# riego.net
KiCad netlist of a schematic drawn in Altium Designer
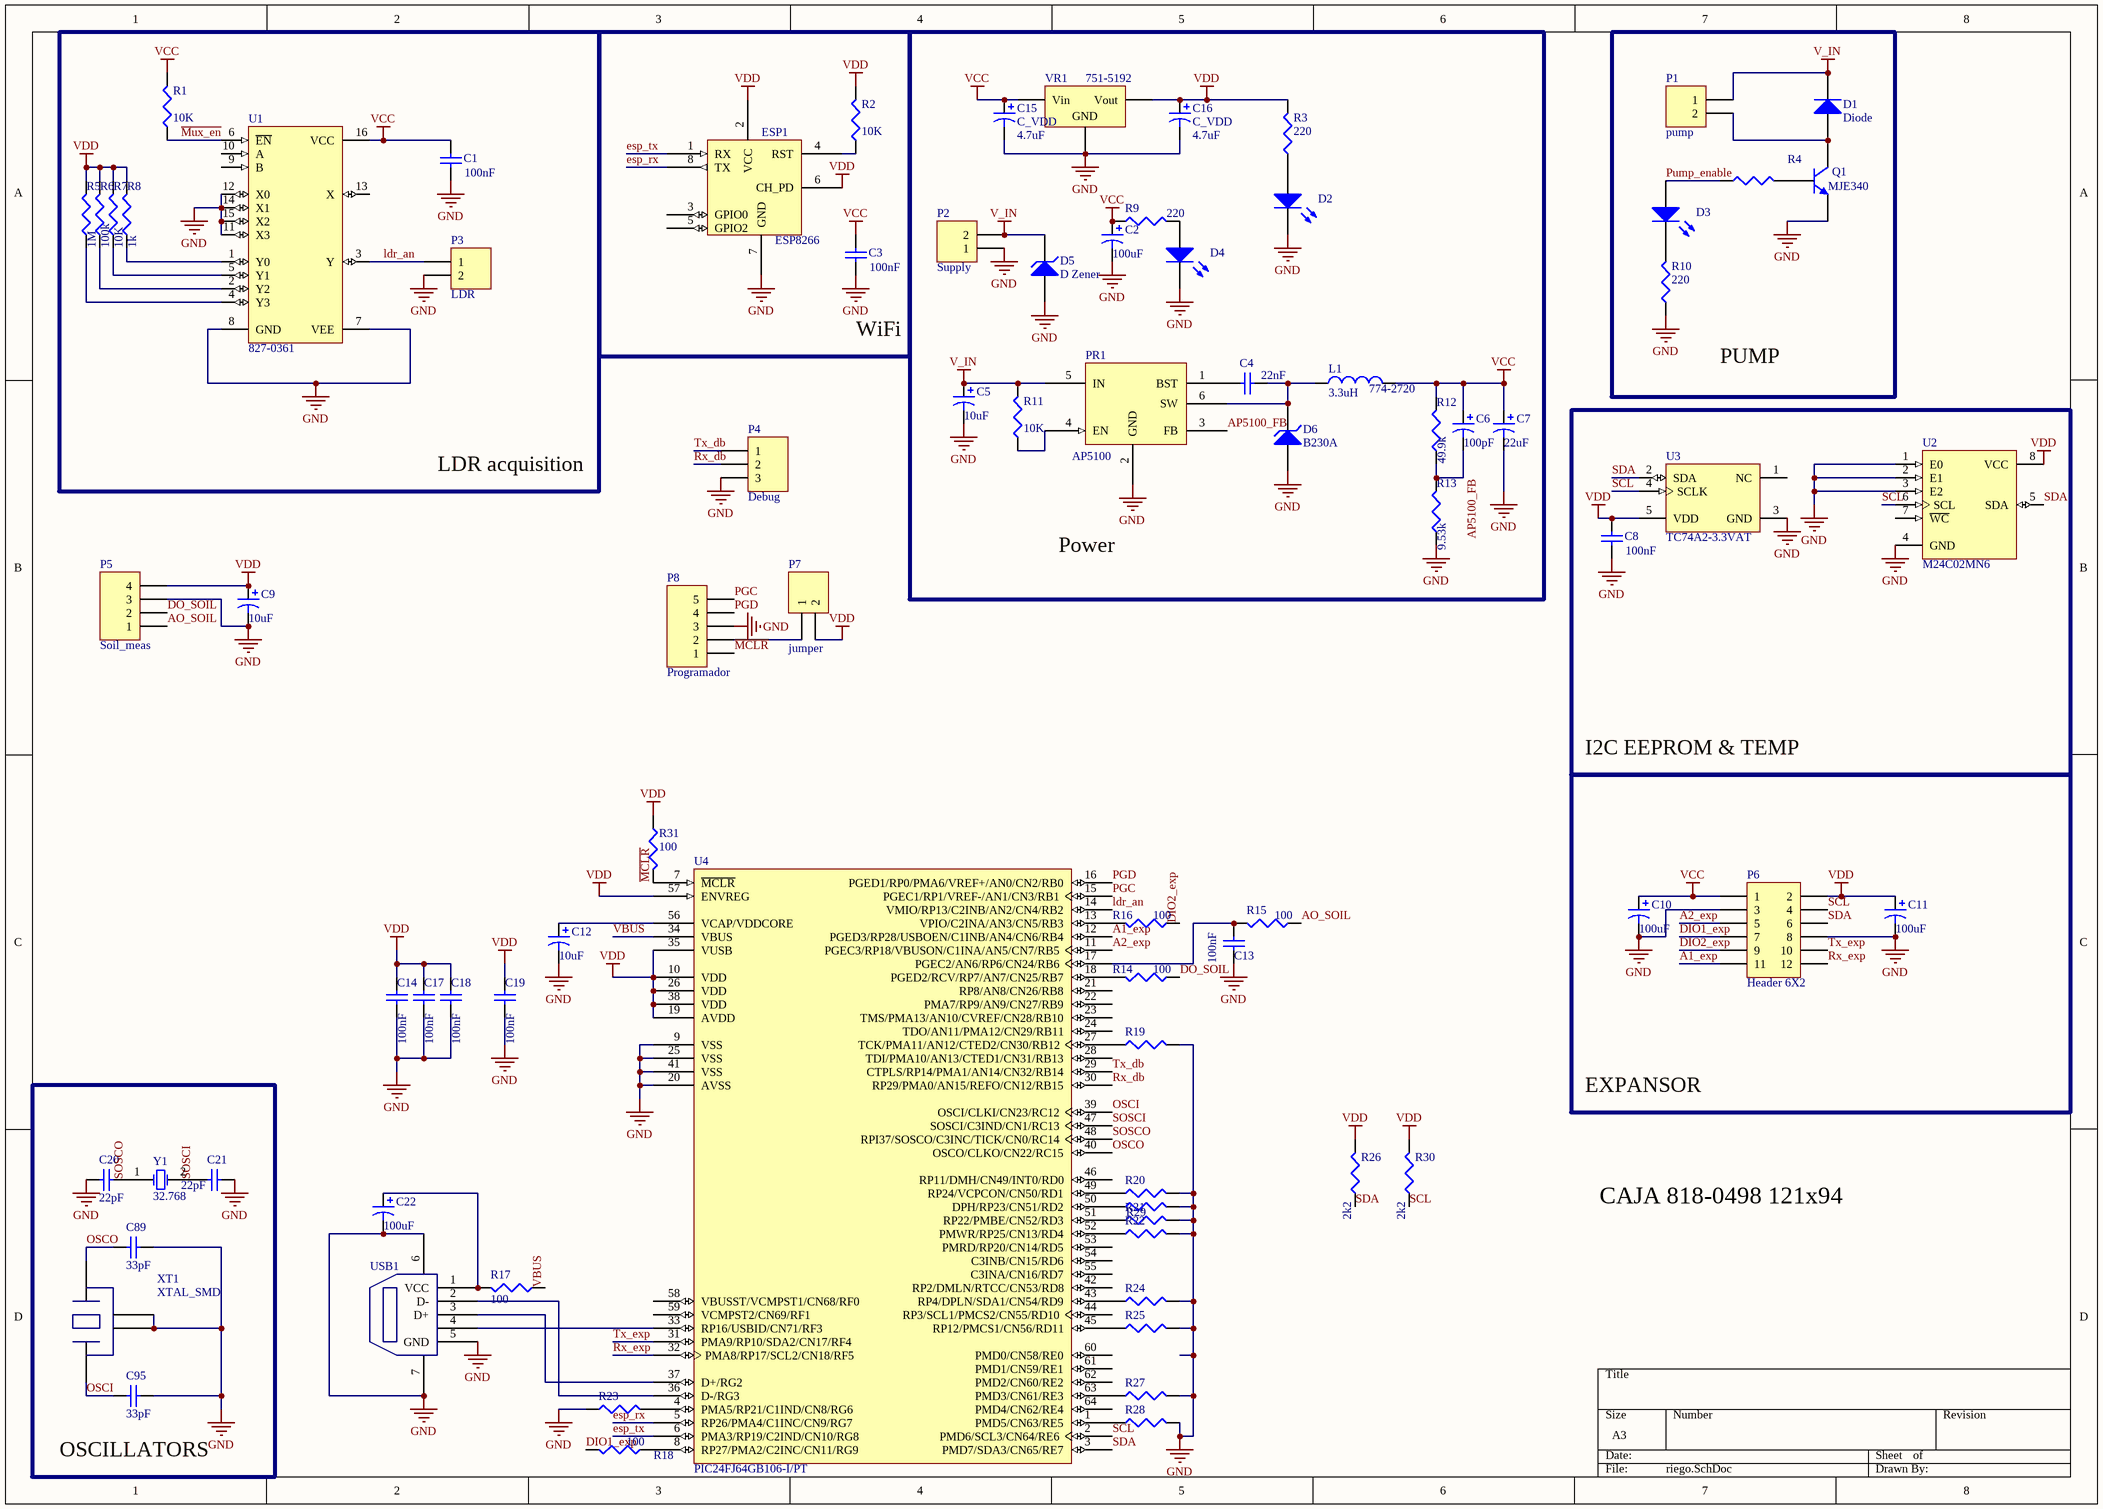
[diagram p0: riego.SchDoc]

(export (version "E")
  (design (tool "Eeschema 10.0.6"))
  (components
    (comp (ref "C1")
      (value "100nF")
      (footprint "CAPC1608L")
      (description "Capacitor (Semiconductor SIM Model)")
      (fields (field (name "Comment") "Cap Semi") (field (name "PUBLISHER") "Altium Limited"))
      (libsource (lib "Miscellaneous Devices") (part "Cap Semi"))
    )
    (comp (ref "C2")
      (value "100uF")
      (footprint "TC3528-1411")
      (description "Polarized Capacitor (Radial)")
      (fields (field (name "PUBLISHER") "Altium Limited"))
      (libsource (lib "Miscellaneous Devices") (part "Cap Pol1"))
    )
    (comp (ref "C3")
      (value "100nF")
      (footprint "CAPC1608L")
      (description "Capacitor (Semiconductor SIM Model)")
      (fields (field (name "Comment") "Cap Semi") (field (name "PUBLISHER") "Altium Limited"))
      (libsource (lib "Miscellaneous Devices") (part "Cap Semi"))
    )
    (comp (ref "C4")
      (value "22nF")
      (footprint "CAPC1608L")
      (description "Capacitor (Semiconductor SIM Model)")
      (fields (field (name "Comment") "Cap Semi") (field (name "PUBLISHER") "Altium Limited"))
      (libsource (lib "Miscellaneous Devices") (part "Cap Semi"))
    )
    (comp (ref "C5")
      (value "10uF")
      (footprint "TC3528-1411")
      (description "Polarized Capacitor (Radial)")
      (fields (field (name "PUBLISHER") "Altium Limited"))
      (libsource (lib "Miscellaneous Devices") (part "Cap Pol1"))
    )
    (comp (ref "C6")
      (value "100pF")
      (footprint "TC3528-1411")
      (description "Polarized Capacitor (Radial)")
      (fields (field (name "PUBLISHER") "Altium Limited"))
      (libsource (lib "Miscellaneous Devices") (part "Cap Pol1"))
    )
    (comp (ref "C7")
      (value "22uF")
      (footprint "TC3528-1411")
      (description "Polarized Capacitor (Radial)")
      (fields (field (name "PUBLISHER") "Altium Limited"))
      (libsource (lib "Miscellaneous Devices") (part "Cap Pol1"))
    )
    (comp (ref "C8")
      (value "100nF")
      (footprint "CAPC1608L")
      (description "Capacitor (Semiconductor SIM Model)")
      (fields (field (name "Comment") "Cap Semi") (field (name "PUBLISHER") "Altium Limited"))
      (libsource (lib "Miscellaneous Devices") (part "Cap Semi"))
    )
    (comp (ref "C9")
      (value "10uF")
      (footprint "TC3528-1411")
      (description "Polarized Capacitor (Radial)")
      (fields (field (name "PUBLISHER") "Altium Limited"))
      (libsource (lib "Miscellaneous Devices") (part "Cap Pol1"))
    )
    (comp (ref "C10")
      (value "100uF")
      (footprint "TC3528-1411")
      (description "Polarized Capacitor (Radial)")
      (fields (field (name "PUBLISHER") "Altium Limited"))
      (libsource (lib "Miscellaneous Devices") (part "Cap Pol1"))
    )
    (comp (ref "C11")
      (value "100uF")
      (footprint "TC3528-1411")
      (description "Polarized Capacitor (Radial)")
      (fields (field (name "PUBLISHER") "Altium Limited"))
      (libsource (lib "Miscellaneous Devices") (part "Cap Pol1"))
    )
    (comp (ref "C12")
      (value "10uF")
      (footprint "TC3528-1411")
      (description "Polarized Capacitor (Radial)")
      (fields (field (name "PUBLISHER") "Altium Limited"))
      (libsource (lib "Miscellaneous Devices") (part "Cap Pol1"))
    )
    (comp (ref "C13")
      (value "100nF")
      (footprint "CAPC1608L")
      (description "Capacitor (Semiconductor SIM Model)")
      (fields (field (name "Comment") "Cap Semi") (field (name "PUBLISHER") "Altium Limited"))
      (libsource (lib "Miscellaneous Devices") (part "Cap Semi"))
    )
    (comp (ref "C14")
      (value "100nF")
      (footprint "CAPC1608L")
      (description "Capacitor (Semiconductor SIM Model)")
      (fields (field (name "Comment") "Cap Semi") (field (name "PUBLISHER") "Altium Limited"))
      (libsource (lib "Miscellaneous Devices") (part "Cap Semi"))
    )
    (comp (ref "C15")
      (value "C_VDD")
      (footprint "CAPC1608N")
      (description "Polarized Capacitor (Radial)")
      (fields (field (name "ALTIUM_VALUE") "4.7uF") (field (name "PUBLISHER") "Altium Limited"))
      (libsource (lib "Miscellaneous Devices") (part "Cap Pol1"))
    )
    (comp (ref "C16")
      (value "C_VDD")
      (footprint "CAPC1608L")
      (description "Polarized Capacitor (Radial)")
      (fields (field (name "ALTIUM_VALUE") "4.7uF") (field (name "PUBLISHER") "Altium Limited"))
      (libsource (lib "Miscellaneous Devices") (part "Cap Pol1"))
    )
    (comp (ref "C17")
      (value "100nF")
      (footprint "CAPC1608L")
      (description "Capacitor (Semiconductor SIM Model)")
      (fields (field (name "Comment") "Cap Semi") (field (name "PUBLISHER") "Altium Limited"))
      (libsource (lib "Miscellaneous Devices") (part "Cap Semi"))
    )
    (comp (ref "C18")
      (value "100nF")
      (footprint "CAPC1608L")
      (description "Capacitor (Semiconductor SIM Model)")
      (fields (field (name "Comment") "Cap Semi") (field (name "PUBLISHER") "Altium Limited"))
      (libsource (lib "Miscellaneous Devices") (part "Cap Semi"))
    )
    (comp (ref "C19")
      (value "100nF")
      (footprint "CAPC1608L")
      (description "Capacitor (Semiconductor SIM Model)")
      (fields (field (name "Comment") "Cap Semi") (field (name "PUBLISHER") "Altium Limited"))
      (libsource (lib "Miscellaneous Devices") (part "Cap Semi"))
    )
    (comp (ref "C20")
      (value "22pF")
      (footprint "C1206")
      (description "Capacitor (Semiconductor SIM Model)")
      (fields (field (name "Comment") "Cap Semi") (field (name "PUBLISHER") "Altium Limited"))
      (libsource (lib "Miscellaneous Devices") (part "Cap Semi"))
    )
    (comp (ref "C21")
      (value "22pF")
      (footprint "C1206")
      (description "Capacitor (Semiconductor SIM Model)")
      (fields (field (name "Comment") "Cap Semi") (field (name "PUBLISHER") "Altium Limited"))
      (libsource (lib "Miscellaneous Devices") (part "Cap Semi"))
    )
    (comp (ref "C22")
      (value "100uF")
      (footprint "TC3528-1411")
      (description "Polarized Capacitor (Radial)")
      (fields (field (name "PUBLISHER") "Altium Limited"))
      (libsource (lib "Miscellaneous Devices") (part "Cap Pol1"))
    )
    (comp (ref "C89")
      (value "33pF")
      (footprint "C1206")
      (description "Capacitor (Semiconductor SIM Model)")
      (fields (field (name "Comment") "Cap Semi") (field (name "PUBLISHER") "Altium Limited"))
      (libsource (lib "Miscellaneous Devices") (part "Cap Semi"))
    )
    (comp (ref "C95")
      (value "33pF")
      (footprint "C1206")
      (description "Capacitor (Semiconductor SIM Model)")
      (fields (field (name "Comment") "Cap Semi") (field (name "PUBLISHER") "Altium Limited"))
      (libsource (lib "Miscellaneous Devices") (part "Cap Semi"))
    )
    (comp (ref "D1")
      (value "Diode")
      (footprint "CD4532-1812")
      (description "Default Diode")
      (fields (field (name "PUBLISHER") "Altium Limited"))
      (libsource (lib "Miscellaneous Devices") (part "Diode"))
    )
    (comp (ref "D2")
      (value "Ledred")
      (footprint "CD1608-0603")
      (description "Typical BLUE SiC LED")
      (fields (field (name "PUBLISHER") "Altium Limited"))
      (libsource (lib "Miscellaneous Devices") (part "LED3"))
    )
    (comp (ref "D3")
      (value "Ledred")
      (footprint "CD1608-0603")
      (description "Typical BLUE SiC LED")
      (fields (field (name "PUBLISHER") "Altium Limited"))
      (libsource (lib "Miscellaneous Devices") (part "LED3"))
    )
    (comp (ref "D4")
      (value "Ledgreen")
      (footprint "CD1608-0603")
      (description "Typical BLUE SiC LED")
      (fields (field (name "PUBLISHER") "Altium Limited"))
      (libsource (lib "Miscellaneous Devices") (part "LED3"))
    )
    (comp (ref "D5")
      (value "D Zener")
      (footprint "CD4532-1812")
      (description "Zener Diode")
      (fields (field (name "PUBLISHER") "Altium Limited"))
      (libsource (lib "Miscellaneous Devices") (part "D Zener"))
    )
    (comp (ref "D6")
      (value "B230A")
      (footprint "CD4532-1812")
      (description "Zener Diode")
      (fields (field (name "PUBLISHER") "Altium Limited"))
      (libsource (lib "Miscellaneous Devices") (part "D Zener"))
    )
    (comp (ref "ESP1") (value "ESP8266") (footprint "ESP8266") (libsource (lib "Mylib") (part "ESP8266")))
    (comp (ref "L1")
      (value "774-2720")
      (footprint "INDC5750N")
      (description "Inductor")
      (fields (field (name "ALTIUM_VALUE") "3.3uH") (field (name "PUBLISHER") "Altium Limited"))
      (libsource (lib "Miscellaneous Devices") (part "Inductor"))
    )
    (comp (ref "P1")
      (value "pump")
      (footprint "Headerx2_5.08")
      (description "Header, 2-Pin")
      (fields (field (name "PUBLISHER") "Altium Limited"))
      (libsource (lib "") (part "Header 2_2"))
    )
    (comp (ref "P2")
      (value "Supply")
      (footprint "JACK_POWER")
      (description "Header, 2-Pin")
      (fields (field (name "PUBLISHER") "Altium Limited"))
      (libsource (lib "") (part "Header 2_3"))
    )
    (comp (ref "P3")
      (value "LDR")
      (footprint "HDR1X2")
      (description "Header, 2-Pin")
      (fields (field (name "PUBLISHER") "Altium Limited"))
      (libsource (lib "Miscellaneous Connectors") (part "Header 2"))
    )
    (comp (ref "P4")
      (value "Debug")
      (footprint "HDR1X3")
      (description "Header, 3-Pin")
      (fields (field (name "PUBLISHER") "Altium Limited"))
      (libsource (lib "Miscellaneous Connectors") (part "Header 3"))
    )
    (comp (ref "P5")
      (value "Soil_meas")
      (footprint "HDR1X4")
      (description "Header, 4-Pin")
      (fields (field (name "PUBLISHER") "Altium Limited"))
      (libsource (lib "Miscellaneous Connectors") (part "Header 4"))
    )
    (comp (ref "P6")
      (value "Header 6X2")
      (footprint "HEADER_SMD_6x2")
      (description "Header, 6-Pin, Dual row")
      (fields (field (name "PUBLISHER") "Altium Limited"))
      (libsource (lib "Miscellaneous Connectors") (part "Header 6X2"))
    )
    (comp (ref "P7")
      (value "jumper")
      (footprint "HDR1X2")
      (description "Header, 2-Pin")
      (fields (field (name "PUBLISHER") "Altium Limited"))
      (libsource (lib "") (part "Header 2_1"))
    )
    (comp (ref "P8")
      (value "Programador")
      (footprint "Header_prog")
      (description "Header, 5-Pin")
      (fields (field (name "PUBLISHER") "Altium Limited"))
      (libsource (lib "Miscellaneous Connectors") (part "Header 5"))
    )
    (comp (ref "PR1")
      (value "AP5100")
      (footprint "SOT26A-6L")
      (description "Step down converter (751-3005)")
      (libsource (lib "Mylib") (part "AP5100"))
    )
    (comp (ref "Q1")
      (value "MJE340")
      (footprint "SOT223-4L")
      (description "Complementary Silicon Power Transistor")
      (fields (field (name "PUBLISHER") "Altium Limited"))
      (libsource (lib "ST Discrete BJT") (part "MJE340"))
    )
    (comp (ref "R1")
      (value "10K")
      (footprint "J1-0603")
      (description "Resistor")
      (fields (field (name "Comment") "Res3") (field (name "PUBLISHER") "Altium Limited"))
      (libsource (lib "Miscellaneous Devices") (part "Res3"))
    )
    (comp (ref "R2")
      (value "10K")
      (footprint "J1-0603")
      (description "Resistor")
      (fields (field (name "Comment") "Res3") (field (name "PUBLISHER") "Altium Limited"))
      (libsource (lib "Miscellaneous Devices") (part "Res3"))
    )
    (comp (ref "R3")
      (value "220")
      (footprint "J1-0603")
      (description "Resistor")
      (fields (field (name "Comment") "Res3") (field (name "PUBLISHER") "Altium Limited"))
      (libsource (lib "Miscellaneous Devices") (part "Res3"))
    )
    (comp (ref "R4")
      (value "Res3")
      (footprint "J1-0603")
      (description "Resistor")
      (fields (field (name "PUBLISHER") "Altium Limited"))
      (libsource (lib "Miscellaneous Devices") (part "Res3"))
    )
    (comp (ref "R5")
      (value "1M")
      (footprint "J1-0603")
      (description "Resistor")
      (fields (field (name "Comment") "Res3") (field (name "PUBLISHER") "Altium Limited"))
      (libsource (lib "Miscellaneous Devices") (part "Res3"))
    )
    (comp (ref "R6")
      (value "100k")
      (footprint "J1-0603")
      (description "Resistor")
      (fields (field (name "Comment") "Res3") (field (name "PUBLISHER") "Altium Limited"))
      (libsource (lib "Miscellaneous Devices") (part "Res3"))
    )
    (comp (ref "R7")
      (value "10K")
      (footprint "J1-0603")
      (description "Resistor")
      (fields (field (name "Comment") "Res3") (field (name "PUBLISHER") "Altium Limited"))
      (libsource (lib "Miscellaneous Devices") (part "Res3"))
    )
    (comp (ref "R8")
      (value "1k")
      (footprint "J1-0603")
      (description "Resistor")
      (fields (field (name "Comment") "Res3") (field (name "PUBLISHER") "Altium Limited"))
      (libsource (lib "Miscellaneous Devices") (part "Res3"))
    )
    (comp (ref "R9")
      (value "220")
      (footprint "J1-0603")
      (description "Resistor")
      (fields (field (name "Comment") "Res3") (field (name "PUBLISHER") "Altium Limited"))
      (libsource (lib "Miscellaneous Devices") (part "Res3"))
    )
    (comp (ref "R10")
      (value "220")
      (footprint "J1-0603")
      (description "Resistor")
      (fields (field (name "Comment") "Res3") (field (name "PUBLISHER") "Altium Limited"))
      (libsource (lib "Miscellaneous Devices") (part "Res3"))
    )
    (comp (ref "R11")
      (value "10K")
      (footprint "J1-0603")
      (description "Resistor")
      (fields (field (name "Comment") "Res3") (field (name "PUBLISHER") "Altium Limited"))
      (libsource (lib "Miscellaneous Devices") (part "Res3"))
    )
    (comp (ref "R12")
      (value "49.9k")
      (footprint "J1-0603")
      (description "Resistor")
      (fields (field (name "Comment") "Res3") (field (name "PUBLISHER") "Altium Limited"))
      (libsource (lib "Miscellaneous Devices") (part "Res3"))
    )
    (comp (ref "R13")
      (value "9.53k")
      (footprint "J1-0603")
      (description "Resistor")
      (fields (field (name "Comment") "Res3") (field (name "PUBLISHER") "Altium Limited"))
      (libsource (lib "Miscellaneous Devices") (part "Res3"))
    )
    (comp (ref "R14")
      (value "100")
      (footprint "J1-0603")
      (description "Resistor")
      (fields (field (name "Comment") "Res3") (field (name "PUBLISHER") "Altium Limited"))
      (libsource (lib "Miscellaneous Devices") (part "Res3"))
    )
    (comp (ref "R15")
      (value "100")
      (footprint "J1-0603")
      (description "Resistor")
      (fields (field (name "Comment") "Res3") (field (name "PUBLISHER") "Altium Limited"))
      (libsource (lib "Miscellaneous Devices") (part "Res3"))
    )
    (comp (ref "R16")
      (value "100")
      (footprint "J1-0603")
      (description "Resistor")
      (fields (field (name "Comment") "Res3") (field (name "PUBLISHER") "Altium Limited"))
      (libsource (lib "Miscellaneous Devices") (part "Res3"))
    )
    (comp (ref "R17")
      (value "100")
      (footprint "J1-0603")
      (description "Resistor")
      (fields (field (name "Comment") "Res3") (field (name "PUBLISHER") "Altium Limited"))
      (libsource (lib "Miscellaneous Devices") (part "Res3"))
    )
    (comp (ref "R18")
      (value "100")
      (footprint "J1-0603")
      (description "Resistor")
      (fields (field (name "Comment") "Res3") (field (name "PUBLISHER") "Altium Limited"))
      (libsource (lib "Miscellaneous Devices") (part "Res3"))
    )
    (comp (ref "R19")
      (value "Res3")
      (footprint "J1-0603")
      (description "Resistor")
      (fields (field (name "PUBLISHER") "Altium Limited"))
      (libsource (lib "Miscellaneous Devices") (part "Res3"))
    )
    (comp (ref "R20")
      (value "Res3")
      (footprint "J1-0603")
      (description "Resistor")
      (fields (field (name "PUBLISHER") "Altium Limited"))
      (libsource (lib "Miscellaneous Devices") (part "Res3"))
    )
    (comp (ref "R21")
      (value "Res3")
      (footprint "J1-0603")
      (description "Resistor")
      (fields (field (name "PUBLISHER") "Altium Limited"))
      (libsource (lib "Miscellaneous Devices") (part "Res3"))
    )
    (comp (ref "R22")
      (value "Res3")
      (footprint "J1-0603")
      (description "Resistor")
      (fields (field (name "PUBLISHER") "Altium Limited"))
      (libsource (lib "Miscellaneous Devices") (part "Res3"))
    )
    (comp (ref "R23")
      (value "Res3")
      (footprint "J1-0603")
      (description "Resistor")
      (fields (field (name "PUBLISHER") "Altium Limited"))
      (libsource (lib "Miscellaneous Devices") (part "Res3"))
    )
    (comp (ref "R24")
      (value "Res3")
      (footprint "J1-0603")
      (description "Resistor")
      (fields (field (name "PUBLISHER") "Altium Limited"))
      (libsource (lib "Miscellaneous Devices") (part "Res3"))
    )
    (comp (ref "R25")
      (value "Res3")
      (footprint "J1-0603")
      (description "Resistor")
      (fields (field (name "PUBLISHER") "Altium Limited"))
      (libsource (lib "Miscellaneous Devices") (part "Res3"))
    )
    (comp (ref "R26")
      (value "2k2")
      (footprint "J1-0603")
      (description "Resistor")
      (fields (field (name "Comment") "Res3") (field (name "PUBLISHER") "Altium Limited"))
      (libsource (lib "Miscellaneous Devices") (part "Res3"))
    )
    (comp (ref "R27")
      (value "Res3")
      (footprint "J1-0603")
      (description "Resistor")
      (fields (field (name "PUBLISHER") "Altium Limited"))
      (libsource (lib "Miscellaneous Devices") (part "Res3"))
    )
    (comp (ref "R28")
      (value "Res3")
      (footprint "J1-0603")
      (description "Resistor")
      (fields (field (name "PUBLISHER") "Altium Limited"))
      (libsource (lib "Miscellaneous Devices") (part "Res3"))
    )
    (comp (ref "R29")
      (value "Res3")
      (footprint "J1-0603")
      (description "Resistor")
      (fields (field (name "PUBLISHER") "Altium Limited"))
      (libsource (lib "Miscellaneous Devices") (part "Res3"))
    )
    (comp (ref "R30")
      (value "2k2")
      (footprint "J1-0603")
      (description "Resistor")
      (fields (field (name "Comment") "Res3") (field (name "PUBLISHER") "Altium Limited"))
      (libsource (lib "Miscellaneous Devices") (part "Res3"))
    )
    (comp (ref "R31")
      (value "100")
      (footprint "J1-0603")
      (description "Resistor")
      (fields (field (name "Comment") "Res3") (field (name "PUBLISHER") "Altium Limited"))
      (libsource (lib "Miscellaneous Devices") (part "Res3"))
    )
    (comp (ref "U1")
      (value "827-0361")
      (footprint "SO16_L")
      (description "Analog Multiplexer/Demultiplexer Dual 4-Channel")
      (fields (field (name "PUBLISHER") "Altium Limited"))
      (libsource (lib "ST Logic Multiplexer") (part "M74HC4052M1R"))
    )
    (comp (ref "U2")
      (value "M24C02MN6")
      (footprint "SOP8_N")
      (description "2Kbit Serial I²C Bus EEPROM")
      (fields (field (name "PUBLISHER") "Altium Limited"))
      (libsource (lib "ST Memory EEPROM Serial") (part "M24C02MN6"))
    )
    (comp (ref "U3")
      (value "TC74A2-3.3VAT")
      (footprint "TO-220-AT5")
      (description "Tiny Serial Digital Thermal Sensor, 5-Pin TO-220, Extended Temperature")
      (fields (field (name "PUBLISHER") "Altium Limited"))
      (libsource (lib "Microchip Thermal Management") (part "TC74A2-3.3VAT"))
    )
    (comp (ref "U4")
      (value "PIC24FJ64GB106-I/PT")
      (footprint "TQFP-PT64_L")
      (fields (field (name "PUBLISHER") "Altium Limited"))
      (libsource (lib "Microchip Microcontroller 16-Bit PIC24F") (part "PIC24FJ64GB106-I/PT"))
    )
    (comp (ref "USB1")
      (value "Micro_USB")
      (footprint "micro_usb")
      (libsource (lib "Mylib") (part "Micro_USB"))
    )
    (comp (ref "VR1")
      (value "751-5192")
      (footprint "DPAK")
      (description "Voltage Regulator")
      (fields (field (name "PUBLISHER") "Altium Limited"))
      (libsource (lib "Miscellaneous Devices") (part "Volt Reg"))
    )
    (comp (ref "XT1")
      (value "XTAL_SMD")
      (footprint "12SMXB-14SMX")
      (libsource (lib "Mylib") (part "XTAL_SMD"))
    )
    (comp (ref "Y1")
      (value "32.768")
      (footprint "BCY-W2/D1.5")
      (description "Crystal Oscillator")
      (fields (field (name "PUBLISHER") "Altium Limited"))
      (libsource (lib "Miscellaneous Devices") (part "XTAL"))
    )
  )
  (nets
    (net (code "1") (name "/A1_exp") (class "Default")
      (node (ref "P6") (pin "11") (pinfunction "11_11") (pintype "passive"))
      (node (ref "U4") (pin "12") (pinfunction "PGED3/RP28/USBOEN/C1INB/AN4/CN6/RB4_12") (pintype "bidirectional"))
    )
    (net (code "2") (name "/A2_exp") (class "Default")
      (node (ref "P6") (pin "5") (pinfunction "5_5") (pintype "passive"))
      (node (ref "U4") (pin "11") (pinfunction "PGEC3/RP18/VBUSON/C1INA/AN5/CN7/RB5_11") (pintype "bidirectional"))
    )
    (net (code "3") (name "/AO_SOIL") (class "Default")
      (node (ref "P5") (pin "1") (pinfunction "1_1") (pintype "passive"))
      (node (ref "R15") (pin "1") (pinfunction "1_1") (pintype "passive"))
    )
    (net (code "4") (name "/AP5100_FB") (class "Default")
      (node (ref "C6") (pin "2") (pinfunction "2_2") (pintype "passive"))
      (node (ref "PR1") (pin "3") (pinfunction "FB_3") (pintype "power_in"))
      (node (ref "R12") (pin "1") (pinfunction "1_1") (pintype "passive"))
      (node (ref "R13") (pin "2") (pinfunction "2_2") (pintype "passive"))
    )
    (net (code "5") (name "/DIO1_exp") (class "Default")
      (node (ref "P6") (pin "7") (pinfunction "7_7") (pintype "passive"))
      (node (ref "R18") (pin "2") (pinfunction "2_2") (pintype "passive"))
    )
    (net (code "6") (name "/DIO2_exp") (class "Default")
      (node (ref "P6") (pin "9") (pinfunction "9_9") (pintype "passive"))
      (node (ref "R16") (pin "1") (pinfunction "1_1") (pintype "passive"))
    )
    (net (code "7") (name "/DO_SOIL") (class "Default")
      (node (ref "P5") (pin "2") (pinfunction "2_2") (pintype "passive"))
      (node (ref "R14") (pin "1") (pinfunction "1_1") (pintype "passive"))
    )
    (net (code "8") (name "/OSCI") (class "Default")
      (node (ref "C95") (pin "2") (pinfunction "2_2") (pintype "passive"))
      (node (ref "U4") (pin "39") (pinfunction "OSCI/CLKI/CN23/RC12_39") (pintype "bidirectional"))
      (node (ref "XT1") (pin "1") (pinfunction "1_1") (pintype "passive"))
    )
    (net (code "9") (name "/OSCO") (class "Default")
      (node (ref "C89") (pin "2") (pinfunction "2_2") (pintype "passive"))
      (node (ref "U4") (pin "40") (pinfunction "OSCO/CLKO/CN22/RC15_40") (pintype "bidirectional"))
      (node (ref "XT1") (pin "3") (pinfunction "3_3") (pintype "passive"))
    )
    (net (code "10") (name "/PGC") (class "Default")
      (node (ref "P8") (pin "5") (pinfunction "5_5") (pintype "passive"))
      (node (ref "U4") (pin "15") (pinfunction "PGEC1/RP1/VREF-/AN1/CN3/RB1_15") (pintype "bidirectional"))
    )
    (net (code "11") (name "/PGD") (class "Default")
      (node (ref "P8") (pin "4") (pinfunction "4_4") (pintype "passive"))
      (node (ref "U4") (pin "16") (pinfunction "PGED1/RP0/PMA6/VREF+/AN0/CN2/RB0_16") (pintype "bidirectional"))
    )
    (net (code "12") (name "/Pump_enable") (class "Default")
      (node (ref "D3") (pin "1") (pinfunction "A_1") (pintype "passive"))
      (node (ref "R4") (pin "1") (pinfunction "1_1") (pintype "passive"))
    )
    (net (code "13") (name "/Rx_db") (class "Default")
      (node (ref "P4") (pin "2") (pinfunction "2_2") (pintype "passive"))
      (node (ref "U4") (pin "30") (pinfunction "RP29/PMA0/AN15/REFO/CN12/RB15_30") (pintype "bidirectional"))
    )
    (net (code "14") (name "/Rx_exp") (class "Default")
      (node (ref "P6") (pin "12") (pinfunction "12_12") (pintype "passive"))
      (node (ref "U4") (pin "32") (pinfunction "PMA8/RP17/SCL2/CN18/RF5_32") (pintype "bidirectional"))
    )
    (net (code "15") (name "/SCL") (class "Default")
      (node (ref "P6") (pin "4") (pinfunction "4_4") (pintype "passive"))
      (node (ref "R30") (pin "1") (pinfunction "1_1") (pintype "passive"))
      (node (ref "U2") (pin "6") (pinfunction "SCL_6") (pintype "input"))
      (node (ref "U3") (pin "4") (pinfunction "SCLK_4") (pintype "input"))
      (node (ref "U4") (pin "2") (pinfunction "PMD6/SCL3/CN64/RE6_2") (pintype "bidirectional"))
    )
    (net (code "16") (name "/SDA") (class "Default")
      (node (ref "P6") (pin "6") (pinfunction "6_6") (pintype "passive"))
      (node (ref "R26") (pin "1") (pinfunction "1_1") (pintype "passive"))
      (node (ref "U2") (pin "5") (pinfunction "SDA_5") (pintype "bidirectional"))
      (node (ref "U3") (pin "2") (pinfunction "SDA_2") (pintype "bidirectional"))
      (node (ref "U4") (pin "3") (pinfunction "PMD7/SDA3/CN65/RE7_3") (pintype "bidirectional"))
    )
    (net (code "17") (name "/SOSCI") (class "Default")
      (node (ref "C21") (pin "2") (pinfunction "2_2") (pintype "passive"))
      (node (ref "U4") (pin "47") (pinfunction "SOSCI/C3IND/CN1/RC13_47") (pintype "bidirectional"))
      (node (ref "Y1") (pin "2") (pinfunction "OSC2_2") (pintype "passive"))
    )
    (net (code "18") (name "/SOSCO") (class "Default")
      (node (ref "C20") (pin "1") (pinfunction "1_1") (pintype "passive"))
      (node (ref "U4") (pin "48") (pinfunction "RPI37/SOSCO/C3INC/TICK/CN0/RC14_48") (pintype "bidirectional"))
      (node (ref "Y1") (pin "1") (pinfunction "OSC1_1") (pintype "passive"))
    )
    (net (code "19") (name "/Tx_db") (class "Default")
      (node (ref "P4") (pin "1") (pinfunction "1_1") (pintype "passive"))
      (node (ref "U4") (pin "29") (pinfunction "CTPLS/RP14/PMA1/AN14/CN32/RB14_29") (pintype "bidirectional"))
    )
    (net (code "20") (name "/Tx_exp") (class "Default")
      (node (ref "P6") (pin "10") (pinfunction "10_10") (pintype "passive"))
      (node (ref "U4") (pin "31") (pinfunction "PMA9/RP10/SDA2/CN17/RF4_31") (pintype "bidirectional"))
    )
    (net (code "21") (name "/VBUS") (class "Default")
      (node (ref "R17") (pin "1") (pinfunction "1_1") (pintype "passive"))
      (node (ref "U4") (pin "34") (pinfunction "VBUS_34") (pintype "power_in"))
    )
    (net (code "22") (name "/esp_rx") (class "Default")
      (node (ref "ESP1") (pin "8") (pinfunction "TX_8") (pintype "output"))
      (node (ref "U4") (pin "5") (pinfunction "RP26/PMA4/C1INC/CN9/RG7_5") (pintype "bidirectional"))
    )
    (net (code "23") (name "/esp_tx") (class "Default")
      (node (ref "ESP1") (pin "1") (pinfunction "RX_1") (pintype "input"))
      (node (ref "U4") (pin "6") (pinfunction "PMA3/RP19/C2IND/CN10/RG8_6") (pintype "bidirectional"))
    )
    (net (code "24") (name "/ldr_an") (class "Default")
      (node (ref "P3") (pin "1") (pinfunction "1_1") (pintype "passive"))
      (node (ref "U1") (pin "3") (pinfunction "Y_3") (pintype "bidirectional"))
      (node (ref "U4") (pin "14") (pinfunction "VMIO/RP13/C2INB/AN2/CN4/RB2_14") (pintype "bidirectional"))
    )
    (net (code "25") (name "/~{MCLR}") (class "Default")
      (node (ref "P8") (pin "1") (pinfunction "1_1") (pintype "passive"))
      (node (ref "R31") (pin "2") (pinfunction "2_2") (pintype "passive"))
      (node (ref "U4") (pin "7") (pinfunction "~{MCLR}_7") (pintype "input"))
    )
    (net (code "26") (name "/~{Mux_en}") (class "Default")
      (node (ref "R1") (pin "1") (pinfunction "1_1") (pintype "passive"))
      (node (ref "U1") (pin "6") (pinfunction "~{EN}_6") (pintype "input"))
    )
    (net (code "27") (name "GND") (class "Default")
      (node (ref "C1") (pin "1") (pinfunction "1_1") (pintype "passive"))
      (node (ref "C10") (pin "2") (pinfunction "2_2") (pintype "passive"))
      (node (ref "C11") (pin "2") (pinfunction "2_2") (pintype "passive"))
      (node (ref "C12") (pin "2") (pinfunction "2_2") (pintype "passive"))
      (node (ref "C13") (pin "1") (pinfunction "1_1") (pintype "passive"))
      (node (ref "C14") (pin "1") (pinfunction "1_1") (pintype "passive"))
      (node (ref "C15") (pin "2") (pinfunction "2_2") (pintype "passive"))
      (node (ref "C16") (pin "2") (pinfunction "2_2") (pintype "passive"))
      (node (ref "C17") (pin "1") (pinfunction "1_1") (pintype "passive"))
      (node (ref "C18") (pin "1") (pinfunction "1_1") (pintype "passive"))
      (node (ref "C19") (pin "1") (pinfunction "1_1") (pintype "passive"))
      (node (ref "C2") (pin "2") (pinfunction "2_2") (pintype "passive"))
      (node (ref "C20") (pin "2") (pinfunction "2_2") (pintype "passive"))
      (node (ref "C21") (pin "1") (pinfunction "1_1") (pintype "passive"))
      (node (ref "C22") (pin "2") (pinfunction "2_2") (pintype "passive"))
      (node (ref "C3") (pin "1") (pinfunction "1_1") (pintype "passive"))
      (node (ref "C5") (pin "2") (pinfunction "2_2") (pintype "passive"))
      (node (ref "C7") (pin "2") (pinfunction "2_2") (pintype "passive"))
      (node (ref "C8") (pin "1") (pinfunction "1_1") (pintype "passive"))
      (node (ref "C89") (pin "1") (pinfunction "1_1") (pintype "passive"))
      (node (ref "C9") (pin "2") (pinfunction "2_2") (pintype "passive"))
      (node (ref "C95") (pin "1") (pinfunction "1_1") (pintype "passive"))
      (node (ref "D2") (pin "2") (pinfunction "K_2") (pintype "passive"))
      (node (ref "D4") (pin "2") (pinfunction "K_2") (pintype "passive"))
      (node (ref "D5") (pin "1") (pinfunction "A_1") (pintype "passive"))
      (node (ref "D6") (pin "1") (pinfunction "A_1") (pintype "passive"))
      (node (ref "ESP1") (pin "7") (pinfunction "GND_7") (pintype "power_in"))
      (node (ref "P2") (pin "1") (pinfunction "1_1") (pintype "passive"))
      (node (ref "P3") (pin "2") (pinfunction "2_2") (pintype "passive"))
      (node (ref "P4") (pin "3") (pinfunction "3_3") (pintype "passive"))
      (node (ref "P5") (pin "3") (pinfunction "3_3") (pintype "passive"))
      (node (ref "P6") (pin "3") (pinfunction "3_3") (pintype "passive"))
      (node (ref "P6") (pin "8") (pinfunction "8_8") (pintype "passive"))
      (node (ref "P8") (pin "3") (pinfunction "3_3") (pintype "passive"))
      (node (ref "PR1") (pin "2") (pinfunction "GND_2") (pintype "power_in"))
      (node (ref "Q1") (pin "3") (pinfunction "E_3") (pintype "passive"))
      (node (ref "R10") (pin "1") (pinfunction "1_1") (pintype "passive"))
      (node (ref "R13") (pin "1") (pinfunction "1_1") (pintype "passive"))
      (node (ref "R19") (pin "2") (pinfunction "2_2") (pintype "passive"))
      (node (ref "R20") (pin "2") (pinfunction "2_2") (pintype "passive"))
      (node (ref "R21") (pin "2") (pinfunction "2_2") (pintype "passive"))
      (node (ref "R22") (pin "2") (pinfunction "2_2") (pintype "passive"))
      (node (ref "R23") (pin "1") (pinfunction "1_1") (pintype "passive"))
      (node (ref "R24") (pin "2") (pinfunction "2_2") (pintype "passive"))
      (node (ref "R25") (pin "2") (pinfunction "2_2") (pintype "passive"))
      (node (ref "R27") (pin "2") (pinfunction "2_2") (pintype "passive"))
      (node (ref "R28") (pin "2") (pinfunction "2_2") (pintype "passive"))
      (node (ref "R29") (pin "2") (pinfunction "2_2") (pintype "passive"))
      (node (ref "U1") (pin "11") (pinfunction "X3_11") (pintype "bidirectional"))
      (node (ref "U1") (pin "12") (pinfunction "X0_12") (pintype "bidirectional"))
      (node (ref "U1") (pin "14") (pinfunction "X1_14") (pintype "bidirectional"))
      (node (ref "U1") (pin "15") (pinfunction "X2_15") (pintype "bidirectional"))
      (node (ref "U1") (pin "7") (pinfunction "VEE_7") (pintype "power_in"))
      (node (ref "U1") (pin "8") (pinfunction "GND_8") (pintype "power_in"))
      (node (ref "U2") (pin "1") (pinfunction "E0_1") (pintype "input"))
      (node (ref "U2") (pin "2") (pinfunction "E1_2") (pintype "input"))
      (node (ref "U2") (pin "3") (pinfunction "E2_3") (pintype "input"))
      (node (ref "U2") (pin "4") (pinfunction "GND_4") (pintype "power_in"))
      (node (ref "U3") (pin "3") (pinfunction "GND_3") (pintype "power_in"))
      (node (ref "U4") (pin "20") (pinfunction "AVSS_20") (pintype "power_in"))
      (node (ref "U4") (pin "25") (pinfunction "VSS_25") (pintype "power_in"))
      (node (ref "U4") (pin "41") (pinfunction "VSS_41") (pintype "power_in"))
      (node (ref "U4") (pin "9") (pinfunction "VSS_9") (pintype "power_in"))
      (node (ref "USB1") (pin "5") (pinfunction "GND_5") (pintype "passive"))
      (node (ref "USB1") (pin "6") (pinfunction "SH_6") (pintype "passive"))
      (node (ref "USB1") (pin "7") (pinfunction "SH_7") (pintype "passive"))
      (node (ref "VR1") (pin "2") (pinfunction "GND_2") (pintype "passive"))
      (node (ref "XT1") (pin "2") (pinfunction "2_2") (pintype "passive"))
      (node (ref "XT1") (pin "4") (pinfunction "4_4") (pintype "passive"))
    )
    (net (code "28") (name "Net-(D1-A)") (class "Default")
      (node (ref "D1") (pin "1") (pinfunction "A_1") (pintype "passive"))
      (node (ref "P1") (pin "2") (pinfunction "2_2") (pintype "passive"))
      (node (ref "Q1") (pin "2") (pinfunction "C_2") (pintype "passive"))
    )
    (net (code "29") (name "Net-(D2-A)") (class "Default")
      (node (ref "D2") (pin "1") (pinfunction "A_1") (pintype "passive"))
      (node (ref "R3") (pin "1") (pinfunction "1_1") (pintype "passive"))
    )
    (net (code "30") (name "Net-(D3-K)") (class "Default")
      (node (ref "D3") (pin "2") (pinfunction "K_2") (pintype "passive"))
      (node (ref "R10") (pin "2") (pinfunction "2_2") (pintype "passive"))
    )
    (net (code "31") (name "Net-(D4-A)") (class "Default")
      (node (ref "D4") (pin "1") (pinfunction "A_1") (pintype "passive"))
      (node (ref "R9") (pin "2") (pinfunction "2_2") (pintype "passive"))
    )
    (net (code "32") (name "Net-(D6-K)") (class "Default")
      (node (ref "C4") (pin "1") (pinfunction "1_1") (pintype "passive"))
      (node (ref "D6") (pin "2") (pinfunction "K_2") (pintype "passive"))
      (node (ref "L1") (pin "1") (pinfunction "1_1") (pintype "passive"))
      (node (ref "PR1") (pin "6") (pinfunction "SW_6") (pintype "power_in"))
    )
    (net (code "33") (name "Net-(ESP1-RST)") (class "Default")
      (node (ref "ESP1") (pin "4") (pinfunction "RST_4") (pintype "passive"))
      (node (ref "R2") (pin "1") (pinfunction "1_1") (pintype "passive"))
    )
    (net (code "34") (name "Net-(P7-Pad1)") (class "Default")
      (node (ref "P7") (pin "1") (pinfunction "1_1") (pintype "passive"))
      (node (ref "P8") (pin "2") (pinfunction "2_2") (pintype "passive"))
    )
    (net (code "35") (name "Net-(PR1-BST)") (class "Default")
      (node (ref "C4") (pin "2") (pinfunction "2_2") (pintype "passive"))
      (node (ref "PR1") (pin "1") (pinfunction "BST_1") (pintype "passive"))
    )
    (net (code "36") (name "Net-(PR1-EN)") (class "Default")
      (node (ref "PR1") (pin "4") (pinfunction "EN_4") (pintype "input"))
      (node (ref "R11") (pin "1") (pinfunction "1_1") (pintype "passive"))
    )
    (net (code "37") (name "Net-(Q1-B)") (class "Default")
      (node (ref "Q1") (pin "1") (pinfunction "B_1") (pintype "passive"))
      (node (ref "R4") (pin "2") (pinfunction "2_2") (pintype "passive"))
    )
    (net (code "38") (name "Net-(U1-Y0)") (class "Default")
      (node (ref "R8") (pin "1") (pinfunction "1_1") (pintype "passive"))
      (node (ref "U1") (pin "1") (pinfunction "Y0_1") (pintype "bidirectional"))
    )
    (net (code "39") (name "Net-(U1-Y1)") (class "Default")
      (node (ref "R7") (pin "1") (pinfunction "1_1") (pintype "passive"))
      (node (ref "U1") (pin "5") (pinfunction "Y1_5") (pintype "bidirectional"))
    )
    (net (code "40") (name "Net-(U1-Y2)") (class "Default")
      (node (ref "R6") (pin "1") (pinfunction "1_1") (pintype "passive"))
      (node (ref "U1") (pin "2") (pinfunction "Y2_2") (pintype "bidirectional"))
    )
    (net (code "41") (name "Net-(U1-Y3)") (class "Default")
      (node (ref "R5") (pin "1") (pinfunction "1_1") (pintype "passive"))
      (node (ref "U1") (pin "4") (pinfunction "Y3_4") (pintype "bidirectional"))
    )
    (net (code "42") (name "Net-(U4-D+{slash}RG2)") (class "Default")
      (node (ref "U4") (pin "37") (pinfunction "D+/RG2_37") (pintype "bidirectional"))
      (node (ref "USB1") (pin "3") (pinfunction "D+_3") (pintype "passive"))
    )
    (net (code "43") (name "Net-(U4-D-{slash}RG3)") (class "Default")
      (node (ref "U4") (pin "36") (pinfunction "D-/RG3_36") (pintype "bidirectional"))
      (node (ref "USB1") (pin "2") (pinfunction "D-_2") (pintype "passive"))
    )
    (net (code "44") (name "Net-(U4-DPH{slash}RP23{slash}CN51{slash}RD2)") (class "Default")
      (node (ref "R29") (pin "1") (pinfunction "1_1") (pintype "passive"))
      (node (ref "U4") (pin "50") (pinfunction "DPH/RP23/CN51/RD2_50") (pintype "bidirectional"))
    )
    (net (code "45") (name "Net-(U4-PGEC2{slash}AN6{slash}RP6{slash}CN24{slash}RB6)") (class "Default")
      (node (ref "C13") (pin "2") (pinfunction "2_2") (pintype "passive"))
      (node (ref "R15") (pin "2") (pinfunction "2_2") (pintype "passive"))
      (node (ref "U4") (pin "17") (pinfunction "PGEC2/AN6/RP6/CN24/RB6_17") (pintype "bidirectional"))
    )
    (net (code "46") (name "Net-(U4-PGED2{slash}RCV{slash}RP7{slash}AN7{slash}CN25{slash}RB7)") (class "Default")
      (node (ref "R14") (pin "2") (pinfunction "2_2") (pintype "passive"))
      (node (ref "U4") (pin "18") (pinfunction "PGED2/RCV/RP7/AN7/CN25/RB7_18") (pintype "bidirectional"))
    )
    (net (code "47") (name "Net-(U4-PMA5{slash}RP21{slash}C1IND{slash}CN8{slash}RG6)") (class "Default")
      (node (ref "R23") (pin "2") (pinfunction "2_2") (pintype "passive"))
      (node (ref "U4") (pin "4") (pinfunction "PMA5/RP21/C1IND/CN8/RG6_4") (pintype "bidirectional"))
    )
    (net (code "48") (name "Net-(U4-PMD3{slash}CN61{slash}RE3)") (class "Default")
      (node (ref "R27") (pin "1") (pinfunction "1_1") (pintype "passive"))
      (node (ref "U4") (pin "63") (pinfunction "PMD3/CN61/RE3_63") (pintype "bidirectional"))
    )
    (net (code "49") (name "Net-(U4-PMD5{slash}CN63{slash}RE5)") (class "Default")
      (node (ref "R28") (pin "1") (pinfunction "1_1") (pintype "passive"))
      (node (ref "U4") (pin "1") (pinfunction "PMD5/CN63/RE5_1") (pintype "bidirectional"))
    )
    (net (code "50") (name "Net-(U4-PMWR{slash}RP25{slash}CN13{slash}RD4)") (class "Default")
      (node (ref "R22") (pin "1") (pinfunction "1_1") (pintype "passive"))
      (node (ref "U4") (pin "52") (pinfunction "PMWR/RP25/CN13/RD4_52") (pintype "bidirectional"))
    )
    (net (code "51") (name "Net-(U4-RP4{slash}DPLN{slash}SDA1{slash}CN54{slash}RD9)") (class "Default")
      (node (ref "R24") (pin "1") (pinfunction "1_1") (pintype "passive"))
      (node (ref "U4") (pin "43") (pinfunction "RP4/DPLN/SDA1/CN54/RD9_43") (pintype "bidirectional"))
    )
    (net (code "52") (name "Net-(U4-RP12{slash}PMCS1{slash}CN56{slash}RD11)") (class "Default")
      (node (ref "R25") (pin "1") (pinfunction "1_1") (pintype "passive"))
      (node (ref "U4") (pin "45") (pinfunction "RP12/PMCS1/CN56/RD11_45") (pintype "bidirectional"))
    )
    (net (code "53") (name "Net-(U4-RP16{slash}USBID{slash}CN71{slash}RF3)") (class "Default")
      (node (ref "U4") (pin "33") (pinfunction "RP16/USBID/CN71/RF3_33") (pintype "bidirectional"))
      (node (ref "USB1") (pin "4") (pintype "passive"))
    )
    (net (code "54") (name "Net-(U4-RP22{slash}PMBE{slash}CN52{slash}RD3)") (class "Default")
      (node (ref "R21") (pin "1") (pinfunction "1_1") (pintype "passive"))
      (node (ref "U4") (pin "51") (pinfunction "RP22/PMBE/CN52/RD3_51") (pintype "bidirectional"))
    )
    (net (code "55") (name "Net-(U4-RP24{slash}VCPCON{slash}CN50{slash}RD1)") (class "Default")
      (node (ref "R20") (pin "1") (pinfunction "1_1") (pintype "passive"))
      (node (ref "U4") (pin "49") (pinfunction "RP24/VCPCON/CN50/RD1_49") (pintype "bidirectional"))
    )
    (net (code "56") (name "Net-(U4-RP27{slash}PMA2{slash}C2INC{slash}CN11{slash}RG9)") (class "Default")
      (node (ref "R18") (pin "1") (pinfunction "1_1") (pintype "passive"))
      (node (ref "U4") (pin "8") (pinfunction "RP27/PMA2/C2INC/CN11/RG9_8") (pintype "bidirectional"))
    )
    (net (code "57") (name "Net-(U4-TCK{slash}PMA11{slash}AN12{slash}CTED2{slash}CN30{slash}RB12)") (class "Default")
      (node (ref "R19") (pin "1") (pinfunction "1_1") (pintype "passive"))
      (node (ref "U4") (pin "27") (pinfunction "TCK/PMA11/AN12/CTED2/CN30/RB12_27") (pintype "bidirectional"))
    )
    (net (code "58") (name "Net-(U4-VCAP{slash}VDDCORE)") (class "Default")
      (node (ref "C12") (pin "1") (pinfunction "1_1") (pintype "passive"))
      (node (ref "U4") (pin "56") (pinfunction "VCAP/VDDCORE_56") (pintype "power_in"))
    )
    (net (code "59") (name "Net-(U4-VPIO{slash}C2INA{slash}AN3{slash}CN5{slash}RB3)") (class "Default")
      (node (ref "R16") (pin "2") (pinfunction "2_2") (pintype "passive"))
      (node (ref "U4") (pin "13") (pinfunction "VPIO/C2INA/AN3/CN5/RB3_13") (pintype "bidirectional"))
    )
    (net (code "60") (name "Net-(USB1-VCC)") (class "Default")
      (node (ref "C22") (pin "1") (pinfunction "1_1") (pintype "passive"))
      (node (ref "R17") (pin "2") (pinfunction "2_2") (pintype "passive"))
      (node (ref "USB1") (pin "1") (pinfunction "VCC_1") (pintype "passive"))
    )
    (net (code "61") (name "VCC") (class "Default")
      (node (ref "C1") (pin "2") (pinfunction "2_2") (pintype "passive"))
      (node (ref "C10") (pin "1") (pinfunction "1_1") (pintype "passive"))
      (node (ref "C15") (pin "1") (pinfunction "1_1") (pintype "passive"))
      (node (ref "C2") (pin "1") (pinfunction "1_1") (pintype "passive"))
      (node (ref "C3") (pin "2") (pinfunction "2_2") (pintype "passive"))
      (node (ref "C6") (pin "1") (pinfunction "1_1") (pintype "passive"))
      (node (ref "C7") (pin "1") (pinfunction "1_1") (pintype "passive"))
      (node (ref "L1") (pin "2") (pinfunction "2_2") (pintype "passive"))
      (node (ref "P6") (pin "1") (pinfunction "1_1") (pintype "passive"))
      (node (ref "R1") (pin "2") (pinfunction "2_2") (pintype "passive"))
      (node (ref "R12") (pin "2") (pinfunction "2_2") (pintype "passive"))
      (node (ref "R9") (pin "1") (pinfunction "1_1") (pintype "passive"))
      (node (ref "U1") (pin "16") (pinfunction "VCC_16") (pintype "power_in"))
      (node (ref "VR1") (pin "1") (pinfunction "Vin_1") (pintype "passive"))
    )
    (net (code "62") (name "VDD") (class "Default")
      (node (ref "C11") (pin "1") (pinfunction "1_1") (pintype "passive"))
      (node (ref "C14") (pin "2") (pinfunction "2_2") (pintype "passive"))
      (node (ref "C16") (pin "1") (pinfunction "1_1") (pintype "passive"))
      (node (ref "C17") (pin "2") (pinfunction "2_2") (pintype "passive"))
      (node (ref "C18") (pin "2") (pinfunction "2_2") (pintype "passive"))
      (node (ref "C19") (pin "2") (pinfunction "2_2") (pintype "passive"))
      (node (ref "C8") (pin "2") (pinfunction "2_2") (pintype "passive"))
      (node (ref "C9") (pin "1") (pinfunction "1_1") (pintype "passive"))
      (node (ref "ESP1") (pin "2") (pinfunction "VCC_2") (pintype "power_in"))
      (node (ref "ESP1") (pin "6") (pinfunction "CH_PD_6") (pintype "passive"))
      (node (ref "P5") (pin "4") (pinfunction "4_4") (pintype "passive"))
      (node (ref "P6") (pin "2") (pinfunction "2_2") (pintype "passive"))
      (node (ref "P7") (pin "2") (pinfunction "2_2") (pintype "passive"))
      (node (ref "R2") (pin "2") (pinfunction "2_2") (pintype "passive"))
      (node (ref "R26") (pin "2") (pinfunction "2_2") (pintype "passive"))
      (node (ref "R3") (pin "2") (pinfunction "2_2") (pintype "passive"))
      (node (ref "R30") (pin "2") (pinfunction "2_2") (pintype "passive"))
      (node (ref "R31") (pin "1") (pinfunction "1_1") (pintype "passive"))
      (node (ref "R5") (pin "2") (pinfunction "2_2") (pintype "passive"))
      (node (ref "R6") (pin "2") (pinfunction "2_2") (pintype "passive"))
      (node (ref "R7") (pin "2") (pinfunction "2_2") (pintype "passive"))
      (node (ref "R8") (pin "2") (pinfunction "2_2") (pintype "passive"))
      (node (ref "U2") (pin "8") (pinfunction "VCC_8") (pintype "power_in"))
      (node (ref "U3") (pin "5") (pinfunction "VDD_5") (pintype "power_in"))
      (node (ref "U4") (pin "10") (pinfunction "VDD_10") (pintype "power_in"))
      (node (ref "U4") (pin "19") (pinfunction "AVDD_19") (pintype "power_in"))
      (node (ref "U4") (pin "26") (pinfunction "VDD_26") (pintype "power_in"))
      (node (ref "U4") (pin "35") (pinfunction "VUSB_35") (pintype "power_in"))
      (node (ref "U4") (pin "38") (pinfunction "VDD_38") (pintype "power_in"))
      (node (ref "U4") (pin "57") (pinfunction "ENVREG_57") (pintype "input"))
      (node (ref "VR1") (pin "3") (pinfunction "Vout_3") (pintype "passive"))
    )
    (net (code "63") (name "V_IN") (class "Default")
      (node (ref "C5") (pin "1") (pinfunction "1_1") (pintype "passive"))
      (node (ref "D1") (pin "2") (pinfunction "K_2") (pintype "passive"))
      (node (ref "D5") (pin "2") (pinfunction "K_2") (pintype "passive"))
      (node (ref "P1") (pin "1") (pinfunction "1_1") (pintype "passive"))
      (node (ref "P2") (pin "2") (pinfunction "2_2") (pintype "passive"))
      (node (ref "PR1") (pin "5") (pinfunction "IN_5") (pintype "power_in"))
      (node (ref "R11") (pin "2") (pinfunction "2_2") (pintype "passive"))
    )
    (net (code "64") (name "unconnected-(ESP1-GPIO0-Pad3)") (class "Default")
      (node (ref "ESP1") (pin "3") (pinfunction "GPIO0_3") (pintype "bidirectional"))
    )
    (net (code "65") (name "unconnected-(ESP1-GPIO2-Pad5)") (class "Default")
      (node (ref "ESP1") (pin "5") (pinfunction "GPIO2_5") (pintype "bidirectional"))
    )
    (net (code "66") (name "unconnected-(U1-A-Pad10)") (class "Default")
      (node (ref "U1") (pin "10") (pinfunction "A_10") (pintype "input"))
    )
    (net (code "67") (name "unconnected-(U1-B-Pad9)") (class "Default")
      (node (ref "U1") (pin "9") (pinfunction "B_9") (pintype "input"))
    )
    (net (code "68") (name "unconnected-(U1-X-Pad13)") (class "Default")
      (node (ref "U1") (pin "13") (pinfunction "X_13") (pintype "bidirectional"))
    )
    (net (code "69") (name "unconnected-(U2-~{WC}-Pad7)") (class "Default")
      (node (ref "U2") (pin "7") (pinfunction "~{WC}_7") (pintype "input"))
    )
    (net (code "70") (name "unconnected-(U3-NC-Pad1)") (class "Default")
      (node (ref "U3") (pin "1") (pinfunction "NC_1") (pintype "passive"))
    )
    (net (code "71") (name "unconnected-(U4-C3INA{slash}CN16{slash}RD7-Pad55)") (class "Default")
      (node (ref "U4") (pin "55") (pinfunction "C3INA/CN16/RD7_55") (pintype "bidirectional"))
    )
    (net (code "72") (name "unconnected-(U4-C3INB{slash}CN15{slash}RD6-Pad54)") (class "Default")
      (node (ref "U4") (pin "54") (pinfunction "C3INB/CN15/RD6_54") (pintype "bidirectional"))
    )
    (net (code "73") (name "unconnected-(U4-PMA7{slash}RP9{slash}AN9{slash}CN27{slash}RB9-Pad22)") (class "Default")
      (node (ref "U4") (pin "22") (pinfunction "PMA7/RP9/AN9/CN27/RB9_22") (pintype "bidirectional"))
    )
    (net (code "74") (name "unconnected-(U4-PMD0{slash}CN58{slash}RE0-Pad60)") (class "Default")
      (node (ref "U4") (pin "60") (pinfunction "PMD0/CN58/RE0_60") (pintype "bidirectional"))
    )
    (net (code "75") (name "unconnected-(U4-PMD1{slash}CN59{slash}RE1-Pad61)") (class "Default")
      (node (ref "U4") (pin "61") (pinfunction "PMD1/CN59/RE1_61") (pintype "bidirectional"))
    )
    (net (code "76") (name "unconnected-(U4-PMD2{slash}CN60{slash}RE2-Pad62)") (class "Default")
      (node (ref "U4") (pin "62") (pinfunction "PMD2/CN60/RE2_62") (pintype "bidirectional"))
    )
    (net (code "77") (name "unconnected-(U4-PMD4{slash}CN62{slash}RE4-Pad64)") (class "Default")
      (node (ref "U4") (pin "64") (pinfunction "PMD4/CN62/RE4_64") (pintype "bidirectional"))
    )
    (net (code "78") (name "unconnected-(U4-PMRD{slash}RP20{slash}CN14{slash}RD5-Pad53)") (class "Default")
      (node (ref "U4") (pin "53") (pinfunction "PMRD/RP20/CN14/RD5_53") (pintype "bidirectional"))
    )
    (net (code "79") (name "unconnected-(U4-RP2{slash}DMLN{slash}RTCC{slash}CN53{slash}RD8-Pad42)") (class "Default")
      (node (ref "U4") (pin "42") (pinfunction "RP2/DMLN/RTCC/CN53/RD8_42") (pintype "bidirectional"))
    )
    (net (code "80") (name "unconnected-(U4-RP3{slash}SCL1{slash}PMCS2{slash}CN55{slash}RD10-Pad44)") (class "Default")
      (node (ref "U4") (pin "44") (pinfunction "RP3/SCL1/PMCS2/CN55/RD10_44") (pintype "bidirectional"))
    )
    (net (code "81") (name "unconnected-(U4-RP8{slash}AN8{slash}CN26{slash}RB8-Pad21)") (class "Default")
      (node (ref "U4") (pin "21") (pinfunction "RP8/AN8/CN26/RB8_21") (pintype "bidirectional"))
    )
    (net (code "82") (name "unconnected-(U4-RP11{slash}DMH{slash}CN49{slash}INT0{slash}RD0-Pad46)") (class "Default")
      (node (ref "U4") (pin "46") (pinfunction "RP11/DMH/CN49/INT0/RD0_46") (pintype "bidirectional"))
    )
    (net (code "83") (name "unconnected-(U4-TDI{slash}PMA10{slash}AN13{slash}CTED1{slash}CN31{slash}RB13-Pad28)") (class "Default")
      (node (ref "U4") (pin "28") (pinfunction "TDI/PMA10/AN13/CTED1/CN31/RB13_28") (pintype "bidirectional"))
    )
    (net (code "84") (name "unconnected-(U4-TDO{slash}AN11{slash}PMA12{slash}CN29{slash}RB11-Pad24)") (class "Default")
      (node (ref "U4") (pin "24") (pinfunction "TDO/AN11/PMA12/CN29/RB11_24") (pintype "bidirectional"))
    )
    (net (code "85") (name "unconnected-(U4-TMS{slash}PMA13{slash}AN10{slash}CVREF{slash}CN28{slash}RB10-Pad23)") (class "Default")
      (node (ref "U4") (pin "23") (pinfunction "TMS/PMA13/AN10/CVREF/CN28/RB10_23") (pintype "bidirectional"))
    )
    (net (code "86") (name "unconnected-(U4-VBUSST{slash}VCMPST1{slash}CN68{slash}RF0-Pad58)") (class "Default")
      (node (ref "U4") (pin "58") (pinfunction "VBUSST/VCMPST1/CN68/RF0_58") (pintype "bidirectional"))
    )
    (net (code "87") (name "unconnected-(U4-VCMPST2{slash}CN69{slash}RF1-Pad59)") (class "Default")
      (node (ref "U4") (pin "59") (pinfunction "VCMPST2/CN69/RF1_59") (pintype "bidirectional"))
    )
  )
)
